# 04_USB7002-PartA.net
KiCad netlist of a schematic drawn in Altium Designer
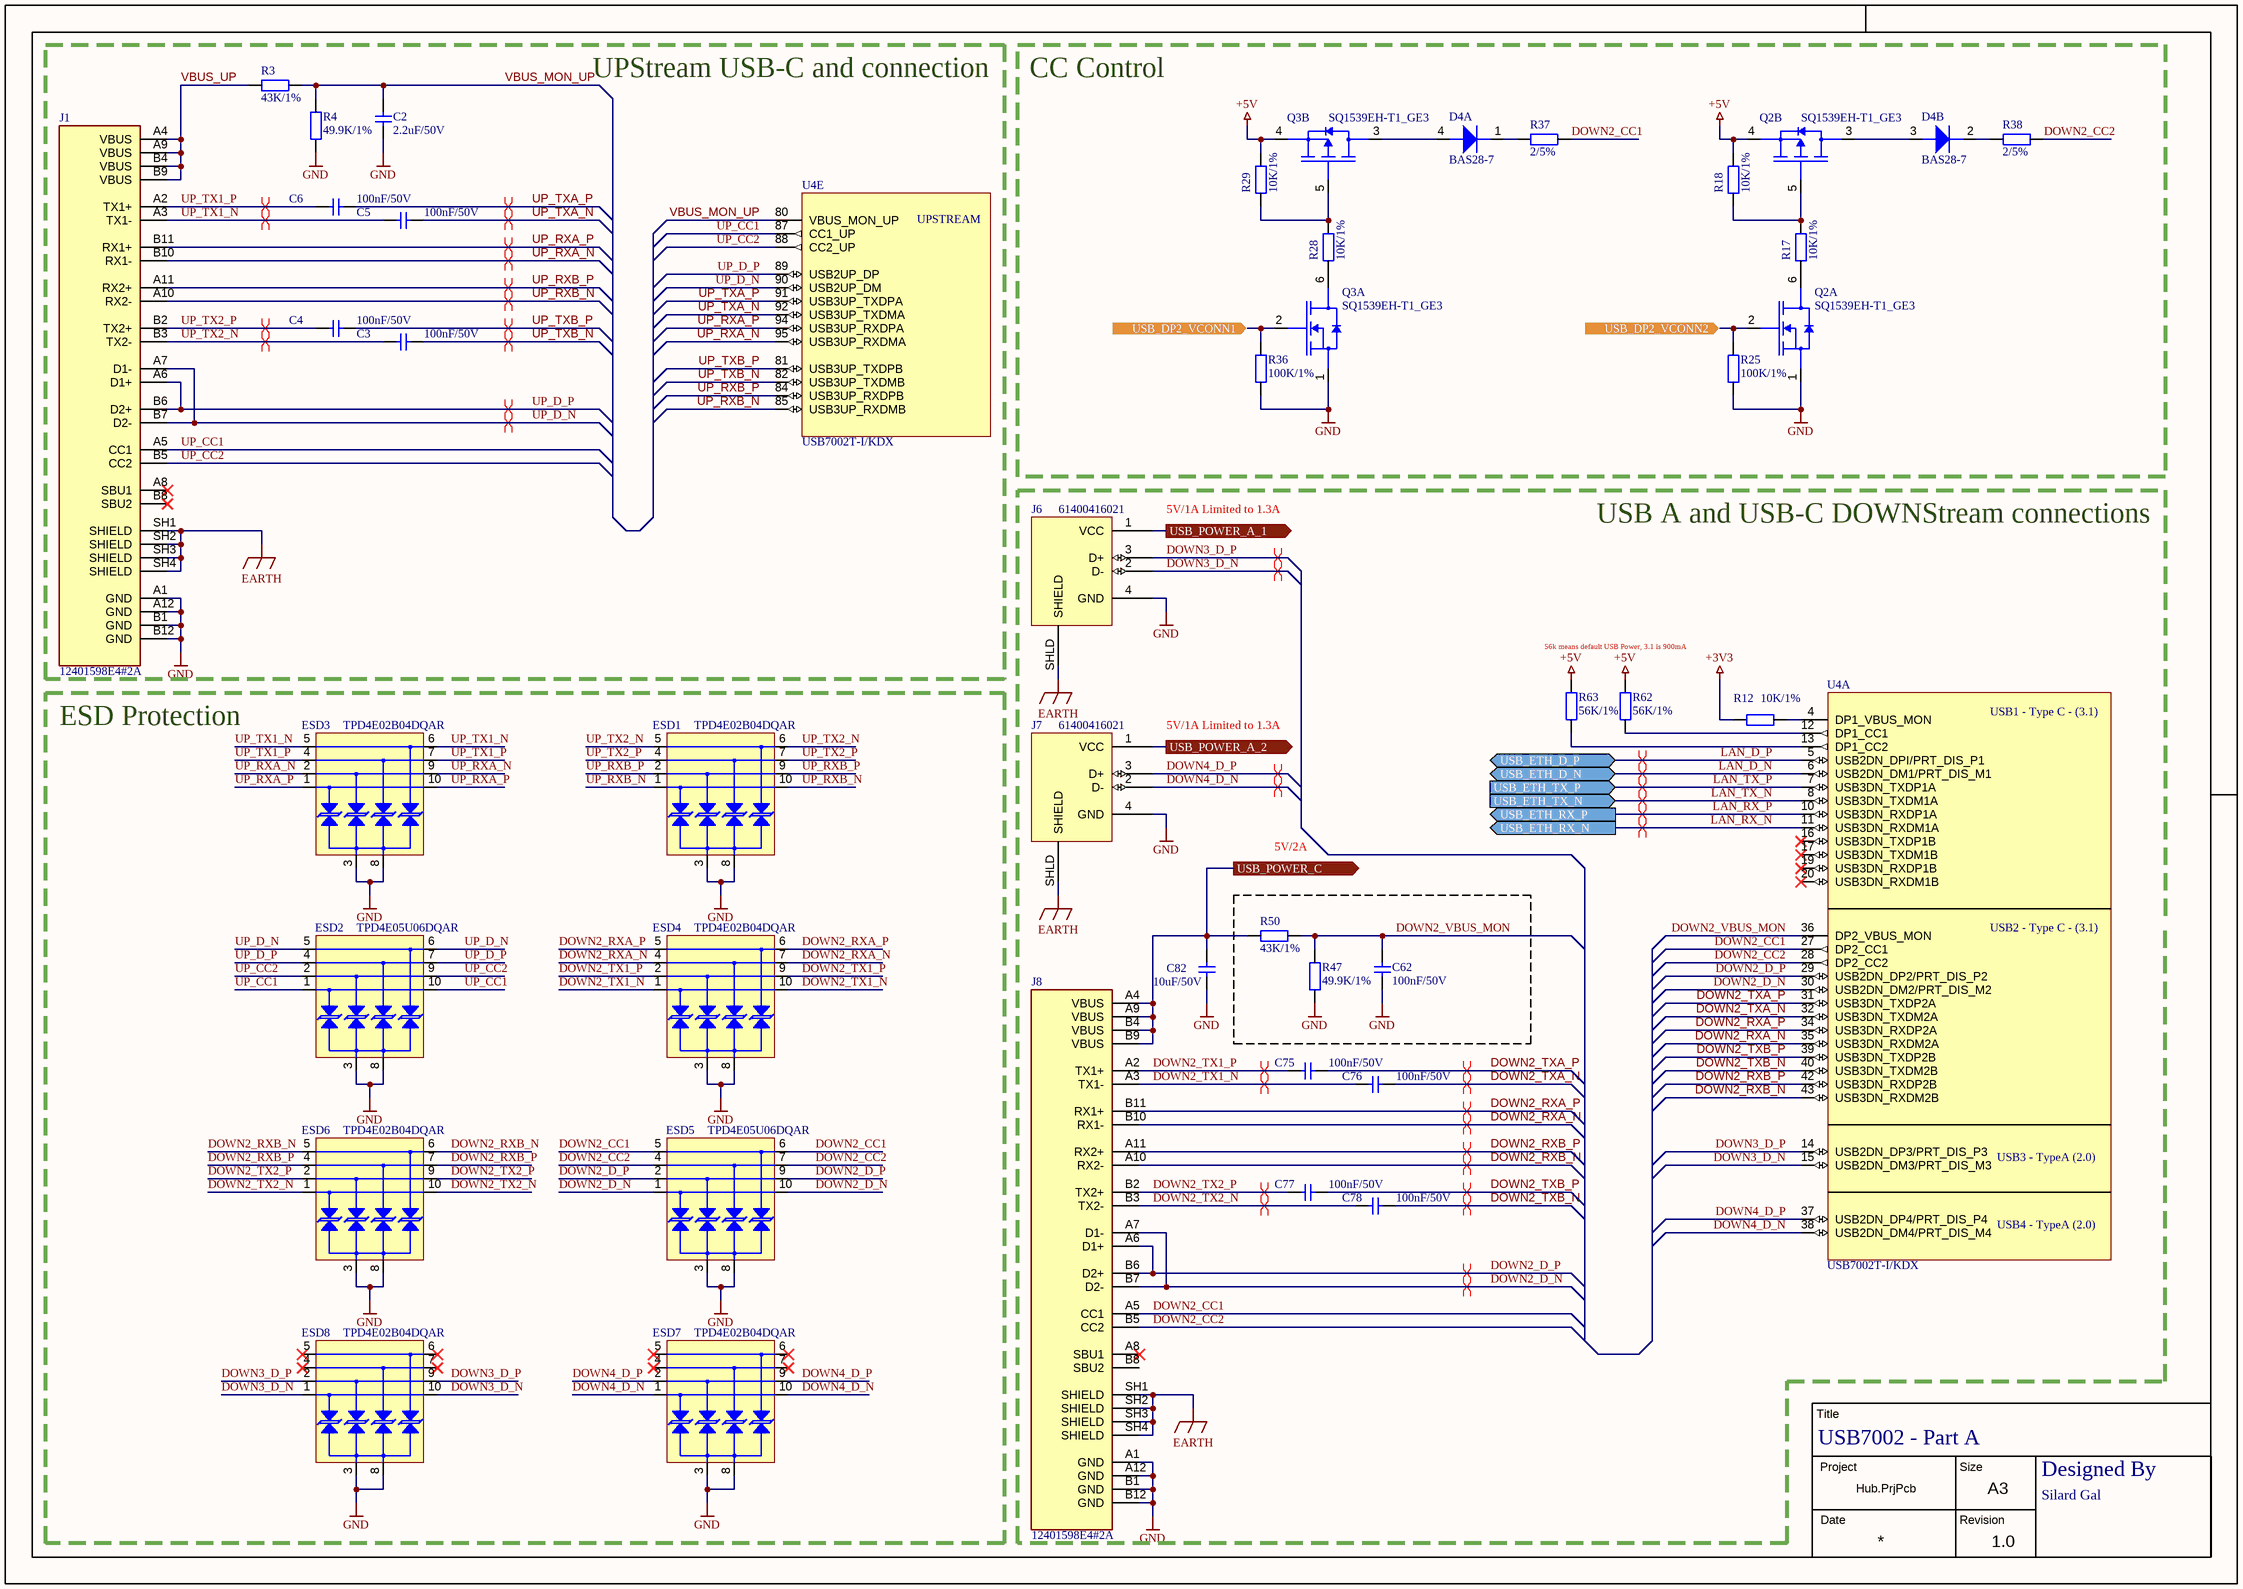
[diagram p0: 04 USB7002-PartA.SchDoc]

(export (version "E")
  (design (tool "Eeschema 10.0.6"))
  (components
    (comp (ref "C2")
      (value "2.2uF/50V")
      (footprint "INDC1608X10N")
      (description "2.2 µF ±20% 50V Ceramic Capacitor X5R 0603 (1608 Metric)")
      (fields
        (field (name "MANUFACTURER") "Murata Electronics")
        (field (name "MFR_PART_NUMBER") "GRT188R61H225ME13D")
      )
      (libsource (lib "altium_symbol") (part "GRT188R61H225ME13D"))
    )
    (comp (ref "C3")
      (value "100nF/50V")
      (footprint "CAPC1005X06N")
      (description "0.1 µF ±10% 50V Ceramic Capacitor X7R 0402 (1005 Metric)")
      (fields
        (field (name "MANUFACTURER") "Murata Electronics")
        (field (name "MFR_PART_NUMBER") "GCM155R71H104KE02J")
      )
      (libsource (lib "altium_symbol") (part "GCM155R71H104KE02J"))
    )
    (comp (ref "C4")
      (value "100nF/50V")
      (footprint "CAPC1005X06N")
      (description "0.1 µF ±10% 50V Ceramic Capacitor X7R 0402 (1005 Metric)")
      (fields
        (field (name "MANUFACTURER") "Murata Electronics")
        (field (name "MFR_PART_NUMBER") "GCM155R71H104KE02J")
      )
      (libsource (lib "altium_symbol") (part "GCM155R71H104KE02J"))
    )
    (comp (ref "C5")
      (value "100nF/50V")
      (footprint "CAPC1005X06N")
      (description "0.1 µF ±10% 50V Ceramic Capacitor X7R 0402 (1005 Metric)")
      (fields
        (field (name "MANUFACTURER") "Murata Electronics")
        (field (name "MFR_PART_NUMBER") "GCM155R71H104KE02J")
      )
      (libsource (lib "altium_symbol") (part "GCM155R71H104KE02J"))
    )
    (comp (ref "C6")
      (value "100nF/50V")
      (footprint "CAPC1005X06N")
      (description "0.1 µF ±10% 50V Ceramic Capacitor X7R 0402 (1005 Metric)")
      (fields
        (field (name "MANUFACTURER") "Murata Electronics")
        (field (name "MFR_PART_NUMBER") "GCM155R71H104KE02J")
      )
      (libsource (lib "altium_symbol") (part "GCM155R71H104KE02J"))
    )
    (comp (ref "C62")
      (value "100nF/50V")
      (footprint "CAPC1005X06N")
      (description "0.1 µF ±10% 50V Ceramic Capacitor X7R 0402 (1005 Metric)")
      (fields
        (field (name "MANUFACTURER") "Murata Electronics")
        (field (name "MFR_PART_NUMBER") "GCM155R71H104KE02J")
      )
      (libsource (lib "altium_symbol") (part "GCM155R71H104KE02J"))
    )
    (comp (ref "C75")
      (value "100nF/50V")
      (footprint "CAPC1005X06N")
      (description "0.1 µF ±10% 50V Ceramic Capacitor X7R 0402 (1005 Metric)")
      (fields
        (field (name "MANUFACTURER") "Murata Electronics")
        (field (name "MFR_PART_NUMBER") "GCM155R71H104KE02J")
      )
      (libsource (lib "altium_symbol") (part "GCM155R71H104KE02J"))
    )
    (comp (ref "C76")
      (value "100nF/50V")
      (footprint "CAPC1005X06N")
      (description "0.1 µF ±10% 50V Ceramic Capacitor X7R 0402 (1005 Metric)")
      (fields
        (field (name "MANUFACTURER") "Murata Electronics")
        (field (name "MFR_PART_NUMBER") "GCM155R71H104KE02J")
      )
      (libsource (lib "altium_symbol") (part "GCM155R71H104KE02J"))
    )
    (comp (ref "C77")
      (value "100nF/50V")
      (footprint "CAPC1005X06N")
      (description "0.1 µF ±10% 50V Ceramic Capacitor X7R 0402 (1005 Metric)")
      (fields
        (field (name "MANUFACTURER") "Murata Electronics")
        (field (name "MFR_PART_NUMBER") "GCM155R71H104KE02J")
      )
      (libsource (lib "altium_symbol") (part "GCM155R71H104KE02J"))
    )
    (comp (ref "C78")
      (value "100nF/50V")
      (footprint "CAPC1005X06N")
      (description "0.1 µF ±10% 50V Ceramic Capacitor X7R 0402 (1005 Metric)")
      (fields
        (field (name "MANUFACTURER") "Murata Electronics")
        (field (name "MFR_PART_NUMBER") "GCM155R71H104KE02J")
      )
      (libsource (lib "altium_symbol") (part "GCM155R71H104KE02J"))
    )
    (comp (ref "C82")
      (value "10uF/50V")
      (footprint "CAPC3216X18N")
      (description "10 µF ±20% 50V Ceramic Capacitor X5R 1206 (3216 Metric)")
      (fields
        (field (name "MANUFACTURER") "Murata Electronics")
        (field (name "MFR_PART_NUMBER") "GRT31CR61H106ME01L")
      )
      (libsource (lib "altium_symbol") (part "GRT31CR61H106ME01L"))
    )
    (comp (ref "D4")
      (value "BAS28-7")
      (footprint "SOT190P238X100-4L")
      (description "Diode Array 2 Independent 85 V 215mA (DC) Surface Mount TO-253-4, TO-253AA")
      (fields (field (name "MANUFACTURER") "Diodes Incorporated"))
      (libsource (lib "altium_symbol") (part "BAS28-7"))
    )
    (comp (ref "ESD1")
      (value "TPD4E02B04DQAR")
      (footprint "USON50P11X26X055")
      (description "8.8V (Typ) Clamp 5A (8/20µs) Ipp Tvs Diode Surface Mount 10-USON (2.5x1)")
      (fields (field (name "MANUFACTURER") "Texas Instruments"))
      (libsource (lib "altium_symbol") (part "TPD4E02B04DQAR"))
    )
    (comp (ref "ESD2")
      (value "TPD4E05U06DQAR")
      (footprint "USON50P11X26X055")
      (description "14V Clamp 2.5A (8/20µs) Ipp Tvs Diode Surface Mount 10-USON (2.5x1)")
      (fields (field (name "MANUFACTURER") "Texas Instruments"))
      (libsource (lib "altium_symbol") (part "TPD4E05U06DQAR"))
    )
    (comp (ref "ESD3")
      (value "TPD4E02B04DQAR")
      (footprint "USON50P11X26X055")
      (description "8.8V (Typ) Clamp 5A (8/20µs) Ipp Tvs Diode Surface Mount 10-USON (2.5x1)")
      (fields (field (name "MANUFACTURER") "Texas Instruments"))
      (libsource (lib "altium_symbol") (part "TPD4E02B04DQAR"))
    )
    (comp (ref "ESD4")
      (value "TPD4E02B04DQAR")
      (footprint "USON50P11X26X055")
      (description "8.8V (Typ) Clamp 5A (8/20µs) Ipp Tvs Diode Surface Mount 10-USON (2.5x1)")
      (fields (field (name "MANUFACTURER") "Texas Instruments"))
      (libsource (lib "altium_symbol") (part "TPD4E02B04DQAR"))
    )
    (comp (ref "ESD5")
      (value "TPD4E05U06DQAR")
      (footprint "USON50P11X26X055")
      (description "14V Clamp 2.5A (8/20µs) Ipp Tvs Diode Surface Mount 10-USON (2.5x1)")
      (fields (field (name "MANUFACTURER") "Texas Instruments"))
      (libsource (lib "altium_symbol") (part "TPD4E05U06DQAR"))
    )
    (comp (ref "ESD6")
      (value "TPD4E02B04DQAR")
      (footprint "USON50P11X26X055")
      (description "8.8V (Typ) Clamp 5A (8/20µs) Ipp Tvs Diode Surface Mount 10-USON (2.5x1)")
      (fields (field (name "MANUFACTURER") "Texas Instruments"))
      (libsource (lib "altium_symbol") (part "TPD4E02B04DQAR"))
    )
    (comp (ref "ESD7")
      (value "TPD4E02B04DQAR")
      (footprint "USON50P11X26X055")
      (description "8.8V (Typ) Clamp 5A (8/20µs) Ipp Tvs Diode Surface Mount 10-USON (2.5x1)")
      (fields (field (name "MANUFACTURER") "Texas Instruments"))
      (libsource (lib "altium_symbol") (part "TPD4E02B04DQAR"))
    )
    (comp (ref "ESD8")
      (value "TPD4E02B04DQAR")
      (footprint "USON50P11X26X055")
      (description "8.8V (Typ) Clamp 5A (8/20µs) Ipp Tvs Diode Surface Mount 10-USON (2.5x1)")
      (fields (field (name "MANUFACTURER") "Texas Instruments"))
      (libsource (lib "altium_symbol") (part "TPD4E02B04DQAR"))
    )
    (comp (ref "J1")
      (value "12401598E4#2A")
      (footprint "12401598E4#2A")
      (fields (field (name "MANUFACTURER") "Amphenol ICC (Commercial Products)"))
      (libsource (lib "altium_symbol") (part "12401598E4#2A"))
    )
    (comp (ref "J6")
      (value "61400416021")
      (footprint "61400416021")
      (description "USB-A (USB TYPE-A) USB 2.0 Receptacle Connector 4 Position Through Hole, Right Angle")
      (fields (field (name "MANUFACTURER") "Würth Elektronik"))
      (libsource (lib "altium_symbol") (part "61400416021"))
    )
    (comp (ref "J7")
      (value "61400416021")
      (footprint "61400416021")
      (description "USB-A (USB TYPE-A) USB 2.0 Receptacle Connector 4 Position Through Hole, Right Angle")
      (fields (field (name "MANUFACTURER") "Würth Elektronik"))
      (libsource (lib "altium_symbol") (part "61400416021"))
    )
    (comp (ref "J8")
      (value "12401598E4#2A")
      (footprint "12401598E4#2A")
      (fields (field (name "MANUFACTURER") "Amphenol ICC (Commercial Products)"))
      (libsource (lib "altium_symbol") (part "12401598E4#2A"))
    )
    (comp (ref "Q2")
      (value "SQ1539EH-T1_GE3")
      (footprint "SOT65P195X110-6N")
      (description "Mosfet Array 30V 850mA (Tc) 1.5W Surface Mount PowerPAK® SC-70-6 Dual")
      (fields (field (name "MANUFACTURER") "Vishay Siliconix"))
      (libsource (lib "") (part "SQ1539EH-T1_GE3_1"))
    )
    (comp (ref "Q3")
      (value "SQ1539EH-T1_GE3")
      (footprint "SOT65P195X110-6N")
      (description "Mosfet Array 30V 850mA (Tc) 1.5W Surface Mount PowerPAK® SC-70-6 Dual")
      (fields (field (name "MANUFACTURER") "Vishay Siliconix"))
      (libsource (lib "altium_symbol") (part "SQ1539EH-T1_GE3"))
    )
    (comp (ref "R3")
      (value "43K/1%")
      (footprint "RESC1005X04N")
      (description "43 kOhms ±1% 0.1W, 1/10W Chip Resistor 0402 (1005 Metric) Automotive AEC-Q200 Thick Film")
      (fields
        (field (name "MANUFACTURER") "Panasonic Electronic Components")
        (field (name "MFR_PART_NUMBER") "ERJ-2RKF4302X")
      )
      (libsource (lib "altium_symbol") (part "ERJ-2RKF4302X"))
    )
    (comp (ref "R4")
      (value "49.9K/1%")
      (footprint "RESC1005X04N")
      (description "49.9 kOhms ±1% 0.1W, 1/10W Chip Resistor 0402 (1005 Metric) Automotive AEC-Q200 Thick Film")
      (fields
        (field (name "MANUFACTURER") "Panasonic Electronic Components")
        (field (name "MFR_PART_NUMBER") "ERJ-2RKF4992X")
      )
      (libsource (lib "altium_symbol") (part "ERJ-2RKF4992X"))
    )
    (comp (ref "R12")
      (value "10K/1%")
      (footprint "RESC1005X04N")
      (description "10 kOhms ±1% 0.063W, 1/16W Chip Resistor 0402 (1005 Metric) Automotive AEC-Q200 Thick Film")
      (fields
        (field (name "MANUFACTURER") "Stackpole Electronics Inc")
        (field (name "MFR_PART_NUMBER") "RMCF0402FT10K0")
      )
      (libsource (lib "altium_symbol") (part "RMCF0402FT10K0"))
    )
    (comp (ref "R17")
      (value "10K/1%")
      (footprint "RESC1005X04N")
      (description "10 kOhms ±1% 0.063W, 1/16W Chip Resistor 0402 (1005 Metric) Automotive AEC-Q200 Thick Film")
      (fields
        (field (name "MANUFACTURER") "Stackpole Electronics Inc")
        (field (name "MFR_PART_NUMBER") "RMCF0402FT10K0")
      )
      (libsource (lib "altium_symbol") (part "RMCF0402FT10K0"))
    )
    (comp (ref "R18")
      (value "10K/1%")
      (footprint "RESC1005X04N")
      (description "10 kOhms ±1% 0.063W, 1/16W Chip Resistor 0402 (1005 Metric) Automotive AEC-Q200 Thick Film")
      (fields
        (field (name "MANUFACTURER") "Stackpole Electronics Inc")
        (field (name "MFR_PART_NUMBER") "RMCF0402FT10K0")
      )
      (libsource (lib "altium_symbol") (part "RMCF0402FT10K0"))
    )
    (comp (ref "R25")
      (value "100K/1%")
      (footprint "RESC1005X04N")
      (description "100 kOhms ±1% 0.063W, 1/16W Chip Resistor 0402 (1005 Metric) Automotive AEC-Q200 Thick Film")
      (fields
        (field (name "MANUFACTURER") "Stackpole Electronics Inc")
        (field (name "MFR_PART_NUMBER") "RMCF0402FT100K")
      )
      (libsource (lib "altium_symbol") (part "RMCF0402FT100K"))
    )
    (comp (ref "R28")
      (value "10K/1%")
      (footprint "RESC1005X04N")
      (description "10 kOhms ±1% 0.063W, 1/16W Chip Resistor 0402 (1005 Metric) Automotive AEC-Q200 Thick Film")
      (fields
        (field (name "MANUFACTURER") "Stackpole Electronics Inc")
        (field (name "MFR_PART_NUMBER") "RMCF0402FT10K0")
      )
      (libsource (lib "altium_symbol") (part "RMCF0402FT10K0"))
    )
    (comp (ref "R29")
      (value "10K/1%")
      (footprint "RESC1005X04N")
      (description "10 kOhms ±1% 0.063W, 1/16W Chip Resistor 0402 (1005 Metric) Automotive AEC-Q200 Thick Film")
      (fields
        (field (name "MANUFACTURER") "Stackpole Electronics Inc")
        (field (name "MFR_PART_NUMBER") "RMCF0402FT10K0")
      )
      (libsource (lib "altium_symbol") (part "RMCF0402FT10K0"))
    )
    (comp (ref "R36")
      (value "100K/1%")
      (footprint "RESC1005X04N")
      (description "100 kOhms ±1% 0.063W, 1/16W Chip Resistor 0402 (1005 Metric) Automotive AEC-Q200 Thick Film")
      (fields
        (field (name "MANUFACTURER") "Stackpole Electronics Inc")
        (field (name "MFR_PART_NUMBER") "RMCF0402FT100K")
      )
      (libsource (lib "altium_symbol") (part "RMCF0402FT100K"))
    )
    (comp (ref "R37")
      (value "2/5%")
      (footprint "RESC1608X04N")
      (fields
        (field (name "MANUFACTURER") "Panasonic Electronic Components")
        (field (name "MFR_PART_NUMBER") "ERJ-PA3J2R0V")
      )
      (libsource (lib "altium_symbol") (part "ERJ-PA3J2R0V"))
    )
    (comp (ref "R38")
      (value "2/5%")
      (footprint "RESC1608X04N")
      (fields
        (field (name "MANUFACTURER") "Panasonic Electronic Components")
        (field (name "MFR_PART_NUMBER") "ERJ-PA3J2R0V")
      )
      (libsource (lib "altium_symbol") (part "ERJ-PA3J2R0V"))
    )
    (comp (ref "R47")
      (value "49.9K/1%")
      (footprint "RESC1005X04N")
      (description "49.9 kOhms ±1% 0.1W, 1/10W Chip Resistor 0402 (1005 Metric) Automotive AEC-Q200 Thick Film")
      (fields
        (field (name "MANUFACTURER") "Panasonic Electronic Components")
        (field (name "MFR_PART_NUMBER") "ERJ-2RKF4992X")
      )
      (libsource (lib "altium_symbol") (part "ERJ-2RKF4992X"))
    )
    (comp (ref "R50")
      (value "43K/1%")
      (footprint "RESC1005X04N")
      (description "43 kOhms ±1% 0.1W, 1/10W Chip Resistor 0402 (1005 Metric) Automotive AEC-Q200 Thick Film")
      (fields
        (field (name "MANUFACTURER") "Panasonic Electronic Components")
        (field (name "MFR_PART_NUMBER") "ERJ-2RKF4302X")
      )
      (libsource (lib "altium_symbol") (part "ERJ-2RKF4302X"))
    )
    (comp (ref "R62")
      (value "56K/1%")
      (footprint "RESC1005X04N")
      (description "56 kOhms ±1% 0.1W, 1/10W Chip Resistor 0402 (1005 Metric) Automotive AEC-Q200 Thick Film")
      (fields
        (field (name "MANUFACTURER") "Panasonic Electronic Components")
        (field (name "MFR_PART_NUMBER") "ERJ-2RKF5602X")
      )
      (libsource (lib "altium_symbol") (part "ERJ-2RKF5602X"))
    )
    (comp (ref "R63")
      (value "56K/1%")
      (footprint "RESC1005X04N")
      (description "56 kOhms ±1% 0.1W, 1/10W Chip Resistor 0402 (1005 Metric) Automotive AEC-Q200 Thick Film")
      (fields
        (field (name "MANUFACTURER") "Panasonic Electronic Components")
        (field (name "MFR_PART_NUMBER") "ERJ-2RKF5602X")
      )
      (libsource (lib "altium_symbol") (part "ERJ-2RKF5602X"))
    )
    (comp (ref "U4")
      (value "USB7002T-I/KDX")
      (footprint "QFN40P1200X1200X90_HS-101N")
      (description "USB Hub Controller USB 3.1 USB Interface 100-VQFN (12x12)")
      (fields (field (name "MANUFACTURER") "Microchip Technology"))
      (libsource (lib "altium_symbol") (part "USB7002T-I/KDX"))
    )
  )
  (nets
    (net (code "1") (name "+3V3") (class "Default")
      (node (ref "R12") (pin "1") (pinfunction "1_1") (pintype "passive"))
    )
    (net (code "2") (name "+5V") (class "Default")
      (node (ref "Q2") (pin "4") (pinfunction "4_4") (pintype "passive"))
      (node (ref "Q3") (pin "4") (pinfunction "4_4") (pintype "passive"))
      (node (ref "R18") (pin "1") (pinfunction "1_1") (pintype "passive"))
      (node (ref "R29") (pin "1") (pinfunction "1_1") (pintype "passive"))
      (node (ref "R62") (pin "1") (pinfunction "1_1") (pintype "passive"))
      (node (ref "R63") (pin "1") (pinfunction "1_1") (pintype "passive"))
    )
    (net (code "3") (name "/DOWN2_CC1") (class "Default")
      (node (ref "ESD5") (pin "5") (pinfunction "IO4_5") (pintype "passive"))
      (node (ref "ESD5") (pin "6") (pinfunction "NC_6") (pintype "passive"))
      (node (ref "J8") (pin "A5") (pinfunction "CC1_A5") (pintype "passive"))
      (node (ref "R37") (pin "2") (pinfunction "2_2") (pintype "passive"))
      (node (ref "U4") (pin "27") (pinfunction "DP2_CC1_27") (pintype "output"))
    )
    (net (code "4") (name "/DOWN2_CC2") (class "Default")
      (node (ref "ESD5") (pin "4") (pinfunction "IO3_4") (pintype "passive"))
      (node (ref "ESD5") (pin "7") (pinfunction "NC_7") (pintype "passive"))
      (node (ref "J8") (pin "B5") (pinfunction "CC2_B5") (pintype "passive"))
      (node (ref "R38") (pin "2") (pinfunction "2_2") (pintype "passive"))
      (node (ref "U4") (pin "28") (pinfunction "DP2_CC2_28") (pintype "output"))
    )
    (net (code "5") (name "/DOWN2_D_N") (class "Default")
      (node (ref "ESD5") (pin "1") (pinfunction "IO1_1") (pintype "passive"))
      (node (ref "ESD5") (pin "10") (pinfunction "NC_10") (pintype "passive"))
      (node (ref "J8") (pin "A7") (pinfunction "D1-_A7") (pintype "passive"))
      (node (ref "J8") (pin "B7") (pinfunction "D2-_B7") (pintype "passive"))
      (node (ref "U4") (pin "30") (pinfunction "USB2DN_DM2/PRT_DIS_M2_30") (pintype "bidirectional"))
    )
    (net (code "6") (name "/DOWN2_D_P") (class "Default")
      (node (ref "ESD5") (pin "2") (pinfunction "IO2_2") (pintype "passive"))
      (node (ref "ESD5") (pin "9") (pinfunction "NC_9") (pintype "passive"))
      (node (ref "J8") (pin "A6") (pinfunction "D1+_A6") (pintype "passive"))
      (node (ref "J8") (pin "B6") (pinfunction "D2+_B6") (pintype "passive"))
      (node (ref "U4") (pin "29") (pinfunction "USB2DN_DP2/PRT_DIS_P2_29") (pintype "bidirectional"))
    )
    (net (code "7") (name "/DOWN2_RXA_N") (class "Default")
      (node (ref "ESD4") (pin "4") (pinfunction "IO3_4") (pintype "passive"))
      (node (ref "ESD4") (pin "7") (pinfunction "NC_7") (pintype "passive"))
      (node (ref "J8") (pin "B10") (pinfunction "RX1-_B10") (pintype "passive"))
      (node (ref "U4") (pin "35") (pinfunction "USB3DN_RXDM2A_35") (pintype "bidirectional"))
    )
    (net (code "8") (name "/DOWN2_RXA_P") (class "Default")
      (node (ref "ESD4") (pin "5") (pinfunction "IO4_5") (pintype "passive"))
      (node (ref "ESD4") (pin "6") (pinfunction "NC_6") (pintype "passive"))
      (node (ref "J8") (pin "B11") (pinfunction "RX1+_B11") (pintype "passive"))
      (node (ref "U4") (pin "34") (pinfunction "USB3DN_RXDP2A_34") (pintype "bidirectional"))
    )
    (net (code "9") (name "/DOWN2_RXB_N") (class "Default")
      (node (ref "ESD6") (pin "5") (pinfunction "IO4_5") (pintype "passive"))
      (node (ref "ESD6") (pin "6") (pinfunction "NC_6") (pintype "passive"))
      (node (ref "J8") (pin "A10") (pinfunction "RX2-_A10") (pintype "passive"))
      (node (ref "U4") (pin "43") (pinfunction "USB3DN_RXDM2B_43") (pintype "bidirectional"))
    )
    (net (code "10") (name "/DOWN2_RXB_P") (class "Default")
      (node (ref "ESD6") (pin "4") (pinfunction "IO3_4") (pintype "passive"))
      (node (ref "ESD6") (pin "7") (pinfunction "NC_7") (pintype "passive"))
      (node (ref "J8") (pin "A11") (pinfunction "RX2+_A11") (pintype "passive"))
      (node (ref "U4") (pin "42") (pinfunction "USB3DN_RXDP2B_42") (pintype "bidirectional"))
    )
    (net (code "11") (name "/DOWN2_TX1_N") (class "Default")
      (node (ref "C76") (pin "2") (pinfunction "2_2") (pintype "passive"))
      (node (ref "ESD4") (pin "1") (pinfunction "IO1_1") (pintype "passive"))
      (node (ref "ESD4") (pin "10") (pinfunction "NC_10") (pintype "passive"))
      (node (ref "J8") (pin "A3") (pinfunction "TX1-_A3") (pintype "passive"))
    )
    (net (code "12") (name "/DOWN2_TX1_P") (class "Default")
      (node (ref "C75") (pin "2") (pinfunction "2_2") (pintype "passive"))
      (node (ref "ESD4") (pin "2") (pinfunction "IO2_2") (pintype "passive"))
      (node (ref "ESD4") (pin "9") (pinfunction "NC_9") (pintype "passive"))
      (node (ref "J8") (pin "A2") (pinfunction "TX1+_A2") (pintype "passive"))
    )
    (net (code "13") (name "/DOWN2_TX2_N") (class "Default")
      (node (ref "C78") (pin "2") (pinfunction "2_2") (pintype "passive"))
      (node (ref "ESD6") (pin "1") (pinfunction "IO1_1") (pintype "passive"))
      (node (ref "ESD6") (pin "10") (pinfunction "NC_10") (pintype "passive"))
      (node (ref "J8") (pin "B3") (pinfunction "TX2-_B3") (pintype "passive"))
    )
    (net (code "14") (name "/DOWN2_TX2_P") (class "Default")
      (node (ref "C77") (pin "2") (pinfunction "2_2") (pintype "passive"))
      (node (ref "ESD6") (pin "2") (pinfunction "IO2_2") (pintype "passive"))
      (node (ref "ESD6") (pin "9") (pinfunction "NC_9") (pintype "passive"))
      (node (ref "J8") (pin "B2") (pinfunction "TX2+_B2") (pintype "passive"))
    )
    (net (code "15") (name "/DOWN2_TXA_N") (class "Default")
      (node (ref "C76") (pin "1") (pinfunction "1_1") (pintype "passive"))
      (node (ref "U4") (pin "32") (pinfunction "USB3DN_TXDM2A_32") (pintype "bidirectional"))
    )
    (net (code "16") (name "/DOWN2_TXA_P") (class "Default")
      (node (ref "C75") (pin "1") (pinfunction "1_1") (pintype "passive"))
      (node (ref "U4") (pin "31") (pinfunction "USB3DN_TXDP2A_31") (pintype "bidirectional"))
    )
    (net (code "17") (name "/DOWN2_TXB_N") (class "Default")
      (node (ref "C78") (pin "1") (pinfunction "1_1") (pintype "passive"))
      (node (ref "U4") (pin "40") (pinfunction "USB3DN_TXDM2B_40") (pintype "bidirectional"))
    )
    (net (code "18") (name "/DOWN2_TXB_P") (class "Default")
      (node (ref "C77") (pin "1") (pinfunction "1_1") (pintype "passive"))
      (node (ref "U4") (pin "39") (pinfunction "USB3DN_TXDP2B_39") (pintype "bidirectional"))
    )
    (net (code "19") (name "/DOWN2_VBUS_MON") (class "Default")
      (node (ref "C62") (pin "1") (pinfunction "1_1") (pintype "passive"))
      (node (ref "R47") (pin "2") (pinfunction "2_2") (pintype "passive"))
      (node (ref "R50") (pin "1") (pinfunction "1_1") (pintype "passive"))
      (node (ref "U4") (pin "36") (pinfunction "DP2_VBUS_MON_36") (pintype "power_in"))
    )
    (net (code "20") (name "/DOWN3_D_N") (class "Default")
      (node (ref "ESD8") (pin "1") (pinfunction "IO1_1") (pintype "passive"))
      (node (ref "ESD8") (pin "10") (pinfunction "NC_10") (pintype "passive"))
      (node (ref "J6") (pin "2") (pinfunction "D-_2") (pintype "bidirectional"))
      (node (ref "U4") (pin "15") (pinfunction "USB2DN_DM3/PRT_DIS_M3_15") (pintype "bidirectional"))
    )
    (net (code "21") (name "/DOWN3_D_P") (class "Default")
      (node (ref "ESD8") (pin "2") (pinfunction "IO2_2") (pintype "passive"))
      (node (ref "ESD8") (pin "9") (pinfunction "NC_9") (pintype "passive"))
      (node (ref "J6") (pin "3") (pinfunction "D+_3") (pintype "bidirectional"))
      (node (ref "U4") (pin "14") (pinfunction "USB2DN_DP3/PRT_DIS_P3_14") (pintype "bidirectional"))
    )
    (net (code "22") (name "/DOWN4_D_N") (class "Default")
      (node (ref "ESD7") (pin "1") (pinfunction "IO1_1") (pintype "passive"))
      (node (ref "ESD7") (pin "10") (pinfunction "NC_10") (pintype "passive"))
      (node (ref "J7") (pin "2") (pinfunction "D-_2") (pintype "bidirectional"))
      (node (ref "U4") (pin "38") (pinfunction "USB2DN_DM4/PRT_DIS_M4_38") (pintype "bidirectional"))
    )
    (net (code "23") (name "/DOWN4_D_P") (class "Default")
      (node (ref "ESD7") (pin "2") (pinfunction "IO2_2") (pintype "passive"))
      (node (ref "ESD7") (pin "9") (pinfunction "NC_9") (pintype "passive"))
      (node (ref "J7") (pin "3") (pinfunction "D+_3") (pintype "bidirectional"))
      (node (ref "U4") (pin "37") (pinfunction "USB2DN_DP4/PRT_DIS_P4_37") (pintype "bidirectional"))
    )
    (net (code "24") (name "/LAN_D_N") (class "Default")
      (node (ref "U4") (pin "6") (pinfunction "USB2DN_DM1/PRT_DIS_M1_6") (pintype "bidirectional"))
    )
    (net (code "25") (name "/LAN_D_P") (class "Default")
      (node (ref "U4") (pin "5") (pinfunction "USB2DN_DPI/PRT_DIS_P1_5") (pintype "bidirectional"))
    )
    (net (code "26") (name "/LAN_RX_N") (class "Default")
      (node (ref "U4") (pin "11") (pinfunction "USB3DN_RXDM1A_11") (pintype "bidirectional"))
    )
    (net (code "27") (name "/LAN_RX_P") (class "Default")
      (node (ref "U4") (pin "10") (pinfunction "USB3DN_RXDP1A_10") (pintype "bidirectional"))
    )
    (net (code "28") (name "/LAN_TX_N") (class "Default")
      (node (ref "U4") (pin "8") (pinfunction "USB3DN_TXDM1A_8") (pintype "bidirectional"))
    )
    (net (code "29") (name "/LAN_TX_P") (class "Default")
      (node (ref "U4") (pin "7") (pinfunction "USB3DN_TXDP1A_7") (pintype "bidirectional"))
    )
    (net (code "30") (name "/UP_CC1") (class "Default")
      (node (ref "ESD2") (pin "1") (pinfunction "IO1_1") (pintype "passive"))
      (node (ref "ESD2") (pin "10") (pinfunction "NC_10") (pintype "passive"))
      (node (ref "J1") (pin "A5") (pinfunction "CC1_A5") (pintype "passive"))
      (node (ref "U4") (pin "87") (pinfunction "CC1_UP_87") (pintype "output"))
    )
    (net (code "31") (name "/UP_CC2") (class "Default")
      (node (ref "ESD2") (pin "2") (pinfunction "IO2_2") (pintype "passive"))
      (node (ref "ESD2") (pin "9") (pinfunction "NC_9") (pintype "passive"))
      (node (ref "J1") (pin "B5") (pinfunction "CC2_B5") (pintype "passive"))
      (node (ref "U4") (pin "88") (pinfunction "CC2_UP_88") (pintype "output"))
    )
    (net (code "32") (name "/UP_D_N") (class "Default")
      (node (ref "ESD2") (pin "5") (pinfunction "IO4_5") (pintype "passive"))
      (node (ref "ESD2") (pin "6") (pinfunction "NC_6") (pintype "passive"))
      (node (ref "J1") (pin "A7") (pinfunction "D1-_A7") (pintype "passive"))
      (node (ref "J1") (pin "B7") (pinfunction "D2-_B7") (pintype "passive"))
      (node (ref "U4") (pin "90") (pinfunction "USB2UP_DM_90") (pintype "bidirectional"))
    )
    (net (code "33") (name "/UP_D_P") (class "Default")
      (node (ref "ESD2") (pin "4") (pinfunction "IO3_4") (pintype "passive"))
      (node (ref "ESD2") (pin "7") (pinfunction "NC_7") (pintype "passive"))
      (node (ref "J1") (pin "A6") (pinfunction "D1+_A6") (pintype "passive"))
      (node (ref "J1") (pin "B6") (pinfunction "D2+_B6") (pintype "passive"))
      (node (ref "U4") (pin "89") (pinfunction "USB2UP_DP_89") (pintype "bidirectional"))
    )
    (net (code "34") (name "/UP_RXA_N") (class "Default")
      (node (ref "ESD3") (pin "2") (pinfunction "IO2_2") (pintype "passive"))
      (node (ref "ESD3") (pin "9") (pinfunction "NC_9") (pintype "passive"))
      (node (ref "J1") (pin "B10") (pinfunction "RX1-_B10") (pintype "passive"))
      (node (ref "U4") (pin "95") (pinfunction "USB3UP_RXDMA_95") (pintype "bidirectional"))
    )
    (net (code "35") (name "/UP_RXA_P") (class "Default")
      (node (ref "ESD3") (pin "1") (pinfunction "IO1_1") (pintype "passive"))
      (node (ref "ESD3") (pin "10") (pinfunction "NC_10") (pintype "passive"))
      (node (ref "J1") (pin "B11") (pinfunction "RX1+_B11") (pintype "passive"))
      (node (ref "U4") (pin "94") (pinfunction "USB3UP_RXDPA_94") (pintype "bidirectional"))
    )
    (net (code "36") (name "/UP_RXB_N") (class "Default")
      (node (ref "ESD1") (pin "1") (pinfunction "IO1_1") (pintype "passive"))
      (node (ref "ESD1") (pin "10") (pinfunction "NC_10") (pintype "passive"))
      (node (ref "J1") (pin "A10") (pinfunction "RX2-_A10") (pintype "passive"))
      (node (ref "U4") (pin "85") (pinfunction "USB3UP_RXDMB_85") (pintype "bidirectional"))
    )
    (net (code "37") (name "/UP_RXB_P") (class "Default")
      (node (ref "ESD1") (pin "2") (pinfunction "IO2_2") (pintype "passive"))
      (node (ref "ESD1") (pin "9") (pinfunction "NC_9") (pintype "passive"))
      (node (ref "J1") (pin "A11") (pinfunction "RX2+_A11") (pintype "passive"))
      (node (ref "U4") (pin "84") (pinfunction "USB3UP_RXDPB_84") (pintype "bidirectional"))
    )
    (net (code "38") (name "/UP_TX1_N") (class "Default")
      (node (ref "C5") (pin "2") (pinfunction "2_2") (pintype "passive"))
      (node (ref "ESD3") (pin "5") (pinfunction "IO4_5") (pintype "passive"))
      (node (ref "ESD3") (pin "6") (pinfunction "NC_6") (pintype "passive"))
      (node (ref "J1") (pin "A3") (pinfunction "TX1-_A3") (pintype "passive"))
    )
    (net (code "39") (name "/UP_TX1_P") (class "Default")
      (node (ref "C6") (pin "2") (pinfunction "2_2") (pintype "passive"))
      (node (ref "ESD3") (pin "4") (pinfunction "IO3_4") (pintype "passive"))
      (node (ref "ESD3") (pin "7") (pinfunction "NC_7") (pintype "passive"))
      (node (ref "J1") (pin "A2") (pinfunction "TX1+_A2") (pintype "passive"))
    )
    (net (code "40") (name "/UP_TX2_N") (class "Default")
      (node (ref "C3") (pin "2") (pinfunction "2_2") (pintype "passive"))
      (node (ref "ESD1") (pin "5") (pinfunction "IO4_5") (pintype "passive"))
      (node (ref "ESD1") (pin "6") (pinfunction "NC_6") (pintype "passive"))
      (node (ref "J1") (pin "B3") (pinfunction "TX2-_B3") (pintype "passive"))
    )
    (net (code "41") (name "/UP_TX2_P") (class "Default")
      (node (ref "C4") (pin "2") (pinfunction "2_2") (pintype "passive"))
      (node (ref "ESD1") (pin "4") (pinfunction "IO3_4") (pintype "passive"))
      (node (ref "ESD1") (pin "7") (pinfunction "NC_7") (pintype "passive"))
      (node (ref "J1") (pin "B2") (pinfunction "TX2+_B2") (pintype "passive"))
    )
    (net (code "42") (name "/UP_TXA_N") (class "Default")
      (node (ref "C5") (pin "1") (pinfunction "1_1") (pintype "passive"))
      (node (ref "U4") (pin "92") (pinfunction "USB3UP_TXDMA_92") (pintype "bidirectional"))
    )
    (net (code "43") (name "/UP_TXA_P") (class "Default")
      (node (ref "C6") (pin "1") (pinfunction "1_1") (pintype "passive"))
      (node (ref "U4") (pin "91") (pinfunction "USB3UP_TXDPA_91") (pintype "bidirectional"))
    )
    (net (code "44") (name "/UP_TXB_N") (class "Default")
      (node (ref "C3") (pin "1") (pinfunction "1_1") (pintype "passive"))
      (node (ref "U4") (pin "82") (pinfunction "USB3UP_TXDMB_82") (pintype "bidirectional"))
    )
    (net (code "45") (name "/UP_TXB_P") (class "Default")
      (node (ref "C4") (pin "1") (pinfunction "1_1") (pintype "passive"))
      (node (ref "U4") (pin "81") (pinfunction "USB3UP_TXDPB_81") (pintype "bidirectional"))
    )
    (net (code "46") (name "/USB_DP2_VCONN1") (class "Default")
      (node (ref "Q3") (pin "2") (pinfunction "S2_2") (pintype "passive"))
      (node (ref "R36") (pin "1") (pinfunction "1_1") (pintype "passive"))
    )
    (net (code "47") (name "/USB_DP2_VCONN2") (class "Default")
      (node (ref "Q2") (pin "2") (pinfunction "S2_2") (pintype "passive"))
      (node (ref "R25") (pin "1") (pinfunction "1_1") (pintype "passive"))
    )
    (net (code "48") (name "/USB_POWER_A_1") (class "Default")
      (node (ref "J6") (pin "1") (pinfunction "VCC_1") (pintype "power_in"))
    )
    (net (code "49") (name "/USB_POWER_A_2") (class "Default")
      (node (ref "J7") (pin "1") (pinfunction "VCC_1") (pintype "power_in"))
    )
    (net (code "50") (name "/USB_POWER_C") (class "Default")
      (node (ref "C82") (pin "2") (pinfunction "2_2") (pintype "passive"))
      (node (ref "J8") (pin "A4") (pinfunction "VBUS_A4") (pintype "power_in"))
      (node (ref "J8") (pin "A9") (pinfunction "VBUS_A9") (pintype "power_in"))
      (node (ref "J8") (pin "B4") (pinfunction "VBUS_B4") (pintype "power_in"))
      (node (ref "J8") (pin "B9") (pinfunction "VBUS_B9") (pintype "power_in"))
      (node (ref "R50") (pin "2") (pinfunction "2_2") (pintype "passive"))
    )
    (net (code "51") (name "/VBUS_MON_UP") (class "Default")
      (node (ref "C2") (pin "2") (pinfunction "2_2") (pintype "passive"))
      (node (ref "R3") (pin "1") (pinfunction "1_1") (pintype "passive"))
      (node (ref "R4") (pin "2") (pinfunction "2_2") (pintype "passive"))
      (node (ref "U4") (pin "80") (pinfunction "VBUS_MON_UP_80") (pintype "passive"))
    )
    (net (code "52") (name "/VBUS_UP") (class "Default")
      (node (ref "J1") (pin "A4") (pinfunction "VBUS_A4") (pintype "power_in"))
      (node (ref "J1") (pin "A9") (pinfunction "VBUS_A9") (pintype "power_in"))
      (node (ref "J1") (pin "B4") (pinfunction "VBUS_B4") (pintype "power_in"))
      (node (ref "J1") (pin "B9") (pinfunction "VBUS_B9") (pintype "power_in"))
      (node (ref "R3") (pin "2") (pinfunction "2_2") (pintype "passive"))
    )
    (net (code "53") (name "EARTH") (class "Default")
      (node (ref "J1") (pin "SH1") (pinfunction "SHIELD_SH1") (pintype "power_in"))
      (node (ref "J1") (pin "SH2") (pinfunction "SHIELD_SH2") (pintype "power_in"))
      (node (ref "J1") (pin "SH3") (pinfunction "SHIELD_SH3") (pintype "power_in"))
      (node (ref "J1") (pin "SH4") (pinfunction "SHIELD_SH4") (pintype "power_in"))
      (node (ref "J6") (pin "SHLD") (pinfunction "SHIELD_SHLD") (pintype "passive"))
      (node (ref "J7") (pin "SHLD") (pinfunction "SHIELD_SHLD") (pintype "passive"))
      (node (ref "J8") (pin "SH1") (pinfunction "SHIELD_SH1") (pintype "power_in"))
      (node (ref "J8") (pin "SH2") (pinfunction "SHIELD_SH2") (pintype "power_in"))
      (node (ref "J8") (pin "SH3") (pinfunction "SHIELD_SH3") (pintype "power_in"))
      (node (ref "J8") (pin "SH4") (pinfunction "SHIELD_SH4") (pintype "power_in"))
    )
    (net (code "54") (name "GND") (class "Default")
      (node (ref "C2") (pin "1") (pinfunction "1_1") (pintype "passive"))
      (node (ref "C62") (pin "2") (pinfunction "2_2") (pintype "passive"))
      (node (ref "C82") (pin "1") (pinfunction "1_1") (pintype "passive"))
      (node (ref "ESD1") (pin "3") (pinfunction "GND_3") (pintype "passive"))
      (node (ref "ESD1") (pin "8") (pinfunction "GND_8") (pintype "passive"))
      (node (ref "ESD2") (pin "3") (pinfunction "GND_3") (pintype "passive"))
      (node (ref "ESD2") (pin "8") (pinfunction "GND_8") (pintype "passive"))
      (node (ref "ESD3") (pin "3") (pinfunction "GND_3") (pintype "passive"))
      (node (ref "ESD3") (pin "8") (pinfunction "GND_8") (pintype "passive"))
      (node (ref "ESD4") (pin "3") (pinfunction "GND_3") (pintype "passive"))
      (node (ref "ESD4") (pin "8") (pinfunction "GND_8") (pintype "passive"))
      (node (ref "ESD5") (pin "3") (pinfunction "GND_3") (pintype "passive"))
      (node (ref "ESD5") (pin "8") (pinfunction "GND_8") (pintype "passive"))
      (node (ref "ESD6") (pin "3") (pinfunction "GND_3") (pintype "passive"))
      (node (ref "ESD6") (pin "8") (pinfunction "GND_8") (pintype "passive"))
      (node (ref "ESD7") (pin "3") (pinfunction "GND_3") (pintype "passive"))
      (node (ref "ESD7") (pin "8") (pinfunction "GND_8") (pintype "passive"))
      (node (ref "ESD8") (pin "3") (pinfunction "GND_3") (pintype "passive"))
      (node (ref "ESD8") (pin "8") (pinfunction "GND_8") (pintype "passive"))
      (node (ref "J1") (pin "A1") (pinfunction "GND_A1") (pintype "power_in"))
      (node (ref "J1") (pin "A12") (pinfunction "GND_A12") (pintype "power_in"))
      (node (ref "J1") (pin "B1") (pinfunction "GND_B1") (pintype "power_in"))
      (node (ref "J1") (pin "B12") (pinfunction "GND_B12") (pintype "power_in"))
      (node (ref "J6") (pin "4") (pinfunction "GND_4") (pintype "power_in"))
      (node (ref "J7") (pin "4") (pinfunction "GND_4") (pintype "power_in"))
      (node (ref "J8") (pin "A1") (pinfunction "GND_A1") (pintype "power_in"))
      (node (ref "J8") (pin "A12") (pinfunction "GND_A12") (pintype "power_in"))
      (node (ref "J8") (pin "B1") (pinfunction "GND_B1") (pintype "power_in"))
      (node (ref "J8") (pin "B12") (pinfunction "GND_B12") (pintype "power_in"))
      (node (ref "Q2") (pin "1") (pinfunction "S1_1") (pintype "passive"))
      (node (ref "Q3") (pin "1") (pinfunction "S1_1") (pintype "passive"))
      (node (ref "R25") (pin "2") (pinfunction "2_2") (pintype "passive"))
      (node (ref "R36") (pin "2") (pinfunction "2_2") (pintype "passive"))
      (node (ref "R4") (pin "1") (pinfunction "1_1") (pintype "passive"))
      (node (ref "R47") (pin "1") (pinfunction "1_1") (pintype "passive"))
    )
    (net (code "55") (name "Net-(D4-Pad1)") (class "Default")
      (node (ref "D4") (pin "1") (pinfunction "1_1") (pintype "passive"))
      (node (ref "R37") (pin "1") (pinfunction "1_1") (pintype "passive"))
    )
    (net (code "56") (name "Net-(D4-Pad2)") (class "Default")
      (node (ref "D4") (pin "2") (pinfunction "2_2") (pintype "passive"))
      (node (ref "R38") (pin "1") (pinfunction "1_1") (pintype "passive"))
    )
    (net (code "57") (name "Net-(D4-Pad3)") (class "Default")
      (node (ref "D4") (pin "3") (pinfunction "3_3") (pintype "passive"))
      (node (ref "Q2") (pin "3") (pinfunction "3_3") (pintype "passive"))
    )
    (net (code "58") (name "Net-(D4-Pad4)") (class "Default")
      (node (ref "D4") (pin "4") (pinfunction "4_4") (pintype "passive"))
      (node (ref "Q3") (pin "3") (pinfunction "3_3") (pintype "passive"))
    )
    (net (code "59") (name "Net-(Q2-Pad5)") (class "Default")
      (node (ref "Q2") (pin "5") (pinfunction "5_5") (pintype "passive"))
      (node (ref "R17") (pin "1") (pinfunction "1_1") (pintype "passive"))
      (node (ref "R18") (pin "2") (pinfunction "2_2") (pintype "passive"))
    )
    (net (code "60") (name "Net-(Q2-Pad6)") (class "Default")
      (node (ref "Q2") (pin "6") (pinfunction "6_6") (pintype "passive"))
      (node (ref "R17") (pin "2") (pinfunction "2_2") (pintype "passive"))
    )
    (net (code "61") (name "Net-(Q3-Pad5)") (class "Default")
      (node (ref "Q3") (pin "5") (pinfunction "5_5") (pintype "passive"))
      (node (ref "R28") (pin "1") (pinfunction "1_1") (pintype "passive"))
      (node (ref "R29") (pin "2") (pinfunction "2_2") (pintype "passive"))
    )
    (net (code "62") (name "Net-(Q3-Pad6)") (class "Default")
      (node (ref "Q3") (pin "6") (pinfunction "6_6") (pintype "passive"))
      (node (ref "R28") (pin "2") (pinfunction "2_2") (pintype "passive"))
    )
    (net (code "63") (name "Net-(U4A-DP1_CC1)") (class "Default")
      (node (ref "R62") (pin "2") (pinfunction "2_2") (pintype "passive"))
      (node (ref "U4") (pin "12") (pinfunction "DP1_CC1_12") (pintype "output"))
    )
    (net (code "64") (name "Net-(U4A-DP1_CC2)") (class "Default")
      (node (ref "R63") (pin "2") (pinfunction "2_2") (pintype "passive"))
      (node (ref "U4") (pin "13") (pinfunction "DP1_CC2_13") (pintype "output"))
    )
    (net (code "65") (name "Net-(U4A-DP1_VBUS_MON)") (class "Default")
      (node (ref "R12") (pin "2") (pinfunction "2_2") (pintype "passive"))
      (node (ref "U4") (pin "4") (pinfunction "DP1_VBUS_MON_4") (pintype "power_in"))
    )
    (net (code "66") (name "unconnected-(ESD7-IO3-Pad4)") (class "Default")
      (node (ref "ESD7") (pin "4") (pinfunction "IO3_4") (pintype "passive+no_connect"))
    )
    (net (code "67") (name "unconnected-(ESD7-IO4-Pad5)") (class "Default")
      (node (ref "ESD7") (pin "5") (pinfunction "IO4_5") (pintype "passive+no_connect"))
    )
    (net (code "68") (name "unconnected-(ESD7-NC-Pad6)") (class "Default")
      (node (ref "ESD7") (pin "6") (pinfunction "NC_6") (pintype "passive+no_connect"))
    )
    (net (code "69") (name "unconnected-(ESD7-NC-Pad7)") (class "Default")
      (node (ref "ESD7") (pin "7") (pinfunction "NC_7") (pintype "passive+no_connect"))
    )
    (net (code "70") (name "unconnected-(ESD8-IO3-Pad4)") (class "Default")
      (node (ref "ESD8") (pin "4") (pinfunction "IO3_4") (pintype "passive+no_connect"))
    )
    (net (code "71") (name "unconnected-(ESD8-IO4-Pad5)") (class "Default")
      (node (ref "ESD8") (pin "5") (pinfunction "IO4_5") (pintype "passive+no_connect"))
    )
    (net (code "72") (name "unconnected-(ESD8-NC-Pad6)") (class "Default")
      (node (ref "ESD8") (pin "6") (pinfunction "NC_6") (pintype "passive+no_connect"))
    )
    (net (code "73") (name "unconnected-(ESD8-NC-Pad7)") (class "Default")
      (node (ref "ESD8") (pin "7") (pinfunction "NC_7") (pintype "passive+no_connect"))
    )
    (net (code "74") (name "unconnected-(J1-SBU1-PadA8)") (class "Default")
      (node (ref "J1") (pin "A8") (pinfunction "SBU1_A8") (pintype "passive+no_connect"))
    )
    (net (code "75") (name "unconnected-(J1-SBU2-PadB8)") (class "Default")
      (node (ref "J1") (pin "B8") (pinfunction "SBU2_B8") (pintype "passive+no_connect"))
    )
    (net (code "76") (name "unconnected-(J8-SBU1-PadA8)") (class "Default")
      (node (ref "J8") (pin "A8") (pinfunction "SBU1_A8") (pintype "passive+no_connect"))
    )
    (net (code "77") (name "unconnected-(J8-SBU2-PadB8)") (class "Default")
      (node (ref "J8") (pin "B8") (pinfunction "SBU2_B8") (pintype "passive"))
    )
    (net (code "78") (name "unconnected-(U4A-USB3DN_RXDM1B-Pad20)") (class "Default")
      (node (ref "U4") (pin "20") (pinfunction "USB3DN_RXDM1B_20") (pintype "bidirectional+no_connect"))
    )
    (net (code "79") (name "unconnected-(U4A-USB3DN_RXDP1B-Pad19)") (class "Default")
      (node (ref "U4") (pin "19") (pinfunction "USB3DN_RXDP1B_19") (pintype "bidirectional+no_connect"))
    )
    (net (code "80") (name "unconnected-(U4A-USB3DN_TXDM1B-Pad17)") (class "Default")
      (node (ref "U4") (pin "17") (pinfunction "USB3DN_TXDM1B_17") (pintype "bidirectional+no_connect"))
    )
    (net (code "81") (name "unconnected-(U4A-USB3DN_TXDP1B-Pad16)") (class "Default")
      (node (ref "U4") (pin "16") (pinfunction "USB3DN_TXDP1B_16") (pintype "bidirectional+no_connect"))
    )
  )
)
